# IRAUPS3.net
KiCad netlist of a schematic drawn in Altium Designer
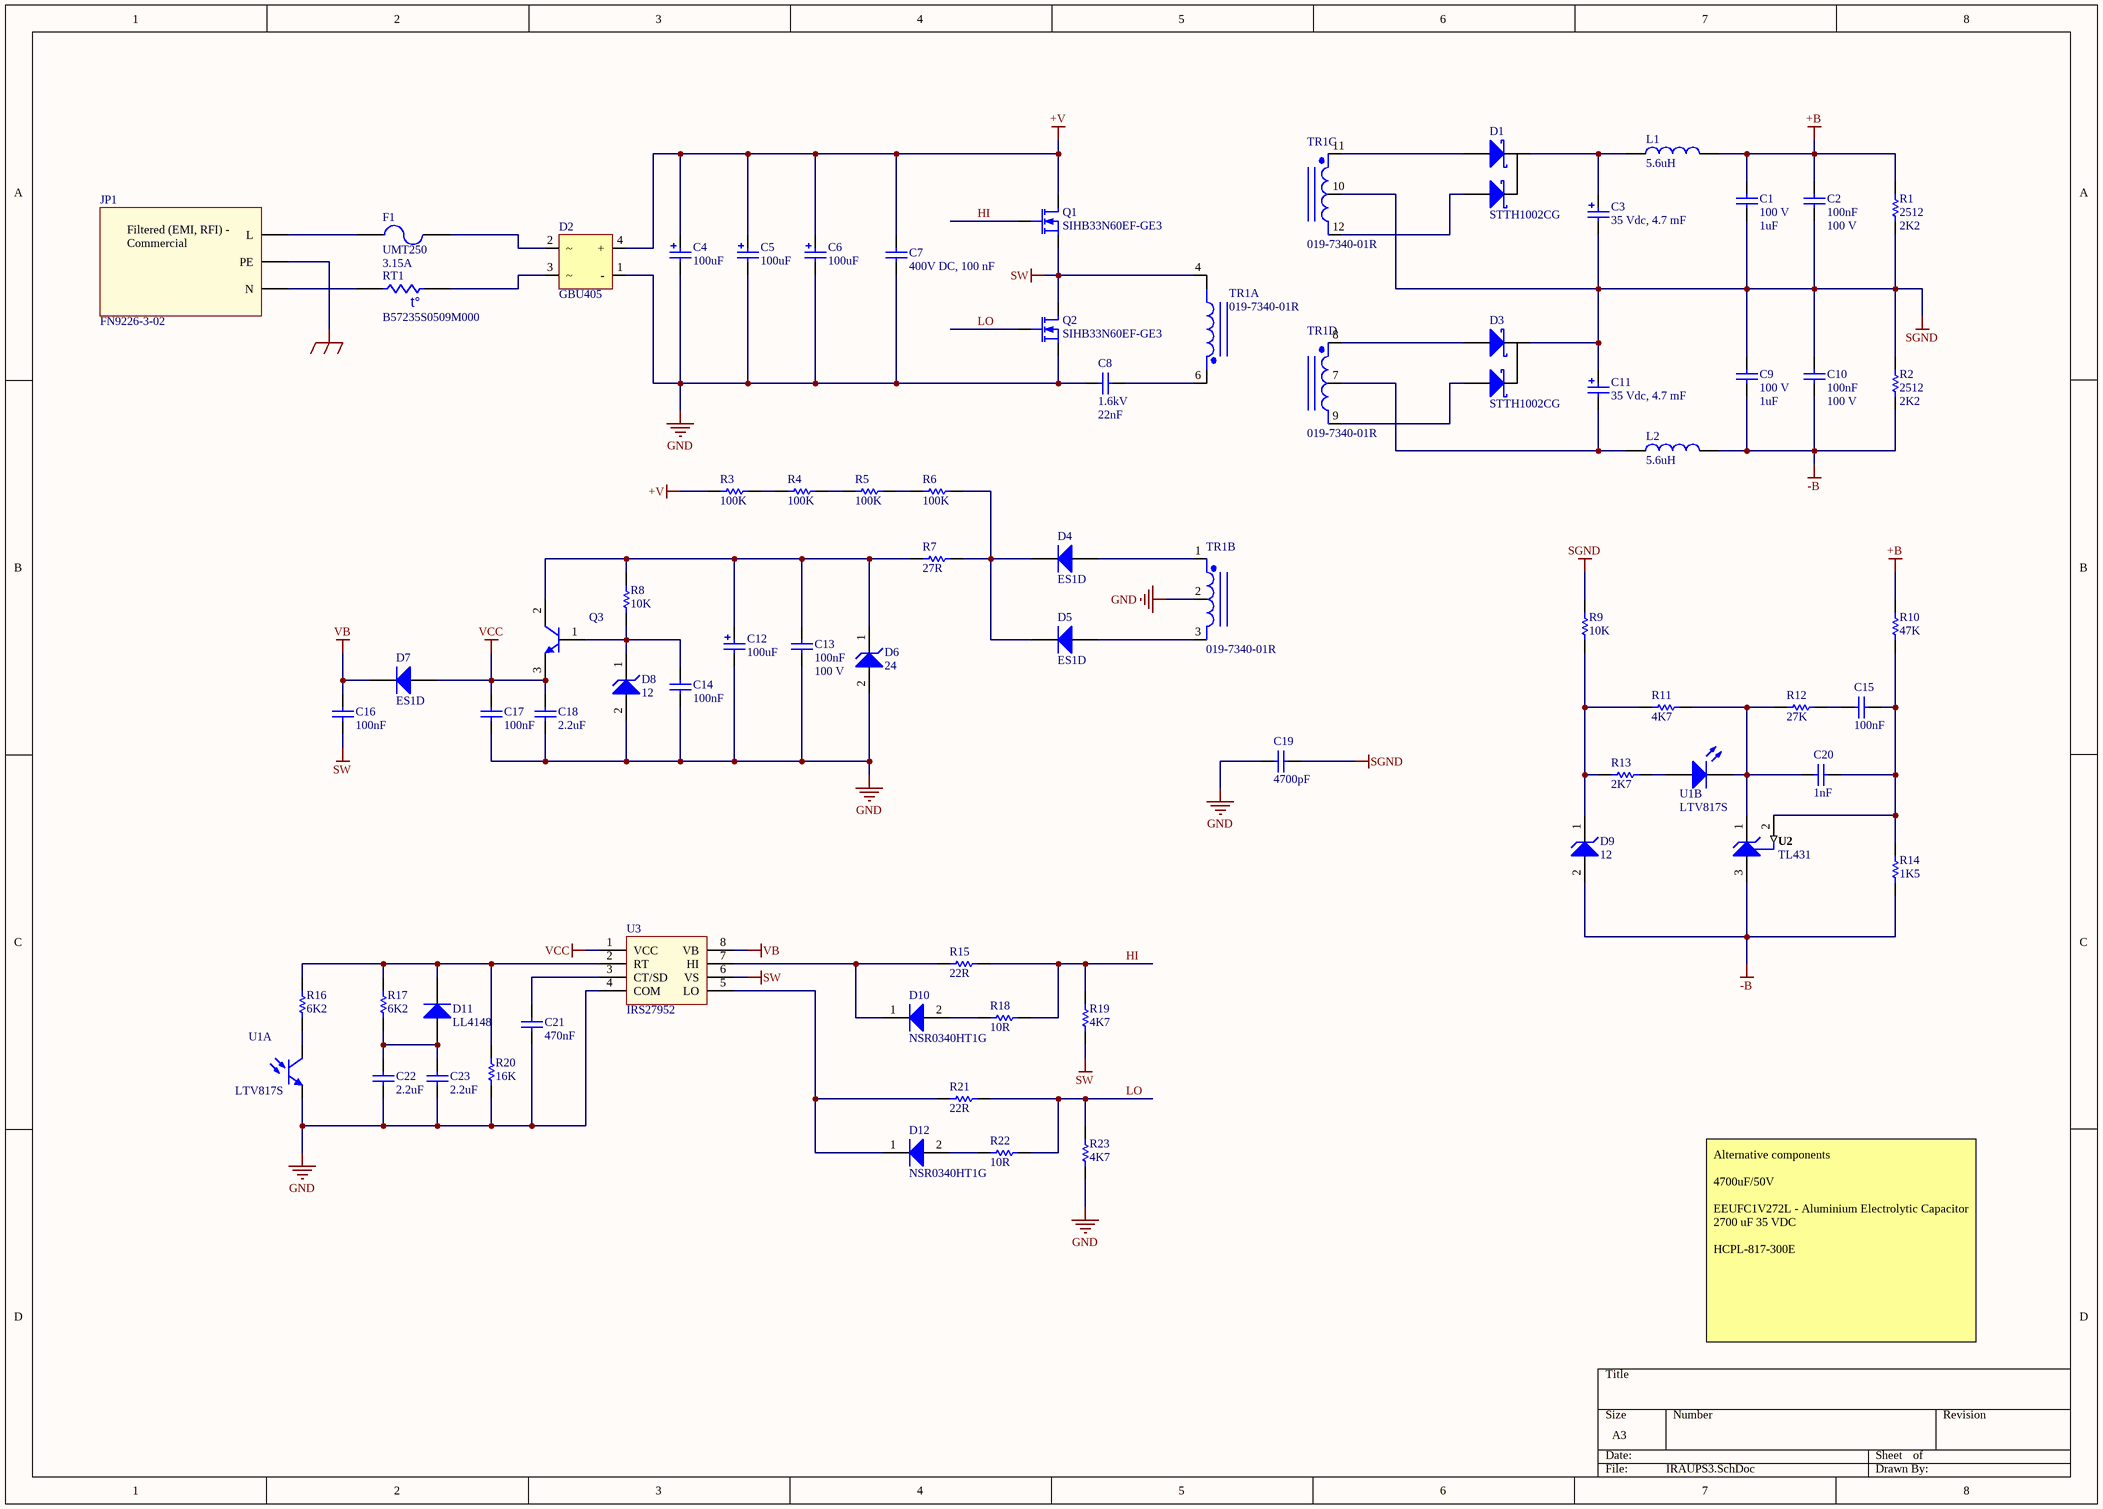
[diagram p0: IRAUPS3.SchDoc]

(export (version "E")
  (design (tool "Eeschema 10.0.6"))
  (components
    (comp (ref "C1")
      (value "1uF")
      (footprint "CAPC1206(3216)190_L")
      (description "CAP 1uF 100V ±20% 1206 (3216 Metric) Thickness 1.9mm SMD")
      (fields
        (field (name "RATED VOLTAGE") "100 V")
        (field (name "TOLERANCE") "Â±20%")
        (field (name "Comment") "CAP 1uF 100V 1206(3216)")
      )
      (libsource (lib "Altium Content Vault") (part "CAP"))
    )
    (comp (ref "C2")
      (value "100nF")
      (footprint "CAPC1206(3216)150_M")
      (description "CAP 100nF 100V ±20% 1206 (3216 Metric) Thickness 1.45mm SMD")
      (fields
        (field (name "TOLERANCE") "Â±20%")
        (field (name "RATED VOLTAGE") "100 V")
        (field (name "Comment") "CAP 100nF 100V 1206(3216)")
      )
      (libsource (lib "Altium Content Vault") (part "CAP"))
    )
    (comp (ref "C3")
      (value "35 Vdc, 4.7 mF")
      (footprint "WCAP-ATG8_18x35.5x7.5")
      (description "WCAP-ATG8 Aluminum Electrolytic Capacitors, 18x35.5mm, 35 Vdc, 4.7 mF")
      (fields (field (name "PART NUMBER") "860010581025") (field (name "PUBLISHER") "Wurth Elektronik"))
      (libsource (lib "ALTIUM-WCAP-ATG8-rev17a") (part "860010581025"))
    )
    (comp (ref "C4")
      (value "100uF")
      (footprint "WCAP-AT1H_16x35.5x7.5")
      (description "WCAP-AT1H Aluminum Electrolytic Capacitors, size Ф16x35.5mm, 450V DC, 100uF")
      (fields (field (name "PART NUMBER") "860241480001") (field (name "PUBLISHER") "Wurth Elektronik"))
      (libsource (lib "ALTIUM-WCAP-AT1H-rev17a") (part "860241480001"))
    )
    (comp (ref "C5")
      (value "100uF")
      (footprint "WCAP-AT1H_16x35.5x7.5")
      (description "WCAP-AT1H Aluminum Electrolytic Capacitors, size Ф16x35.5mm, 450V DC, 100uF")
      (fields (field (name "PART NUMBER") "860241480001") (field (name "PUBLISHER") "Wurth Elektronik"))
      (libsource (lib "ALTIUM-WCAP-AT1H-rev17a") (part "860241480001"))
    )
    (comp (ref "C6")
      (value "100uF")
      (footprint "WCAP-AT1H_16x35.5x7.5")
      (description "WCAP-AT1H Aluminum Electrolytic Capacitors, size Ф16x35.5mm, 450V DC, 100uF")
      (fields (field (name "PART NUMBER") "860241480001") (field (name "PUBLISHER") "Wurth Elektronik"))
      (libsource (lib "ALTIUM-WCAP-AT1H-rev17a") (part "860241480001"))
    )
    (comp (ref "C7")
      (value "400V DC, 100 nF")
      (footprint "WCAP-FTBE_13x5x11")
      (description "WCAP-FTBE Film Capacitors, 13x5x11mm, 400V DC, 100 nF")
      (fields (field (name "PART NUMBER") "890283423001CS") (field (name "PUBLISHER") "Wurth Elektronik"))
      (libsource (lib "ALTIUM-WCAP-FTBE-rev17a") (part "890283423001CS"))
    )
    (comp (ref "C8")
      (value "22nF")
      (footprint "CAP_RM15_W9L18")
      (description "0.022µF Film Capacitor 600V 1600V (1.6kV) Polypropylene (PP), Metallized Radial")
      (fields (field (name "MPN") "B32672L1223J000") (field (name "VOLTAGE") "1.6kV"))
      (libsource (lib "micun") (part "CAP_MKP_B32672L1223J000"))
    )
    (comp (ref "C9")
      (value "1uF")
      (footprint "CAPC1206(3216)190_L")
      (description "CAP 1uF 100V ±20% 1206 (3216 Metric) Thickness 1.9mm SMD")
      (fields
        (field (name "RATED VOLTAGE") "100 V")
        (field (name "TOLERANCE") "Â±20%")
        (field (name "Comment") "CAP 1uF 100V 1206(3216)")
      )
      (libsource (lib "Altium Content Vault") (part "CAP"))
    )
    (comp (ref "C10")
      (value "100nF")
      (footprint "CAPC1206(3216)150_M")
      (description "CAP 100nF 100V ±20% 1206 (3216 Metric) Thickness 1.45mm SMD")
      (fields
        (field (name "TOLERANCE") "Â±20%")
        (field (name "RATED VOLTAGE") "100 V")
        (field (name "Comment") "CAP 100nF 100V 1206(3216)")
      )
      (libsource (lib "Altium Content Vault") (part "CAP"))
    )
    (comp (ref "C11")
      (value "35 Vdc, 4.7 mF")
      (footprint "WCAP-ATG8_18x35.5x7.5")
      (description "WCAP-ATG8 Aluminum Electrolytic Capacitors, 18x35.5mm, 35 Vdc, 4.7 mF")
      (fields (field (name "PART NUMBER") "860010581025") (field (name "PUBLISHER") "Wurth Elektronik"))
      (libsource (lib "ALTIUM-WCAP-ATG8-rev17a") (part "860010581025"))
    )
    (comp (ref "C12")
      (value "100uF")
      (footprint "WCAP-AT1H_8x11.5x3.5")
      (description "WCAP-AT1H Aluminum Electrolytic Capacitors, size Ф8x11.5mm, 25V DC, 100uF")
      (fields (field (name "PART NUMBER") "860240474005") (field (name "PUBLISHER") "Wurth Elektronik"))
      (libsource (lib "ALTIUM-WCAP-AT1H-rev17a") (part "860240474005"))
    )
    (comp (ref "C13")
      (value "100nF")
      (footprint "CAPC1206(3216)150_M")
      (description "CAP 100nF 100V ±20% 1206 (3216 Metric) Thickness 1.45mm SMD")
      (fields
        (field (name "TOLERANCE") "Â±20%")
        (field (name "RATED VOLTAGE") "100 V")
        (field (name "Comment") "CAP 100nF 100V 1206(3216)")
      )
      (libsource (lib "Altium Content Vault") (part "CAP"))
    )
    (comp (ref "C14")
      (value "100nF")
      (footprint "CAPC0805(2012)100_N")
      (description "CAP 100nF 25V ±5% 0805 (2012 Metric) Thickness 1mm SMD")
      (fields (field (name "TOLERANCE") "Â±5%") (field (name "Comment") "CAP 100nF 25V 0805(2012)"))
      (libsource (lib "Altium Content Vault") (part "CAP"))
    )
    (comp (ref "C15")
      (value "100nF")
      (footprint "CAPC0805(2012)100_N")
      (description "CAP 100nF 25V ±5% 0805 (2012 Metric) Thickness 1mm SMD")
      (fields (field (name "TOLERANCE") "Â±5%") (field (name "Comment") "CAP 100nF 25V 0805(2012)"))
      (libsource (lib "Altium Content Vault") (part "CAP"))
    )
    (comp (ref "C16")
      (value "100nF")
      (footprint "CAPC0805(2012)100_N")
      (description "CAP 100nF 25V ±5% 0805 (2012 Metric) Thickness 1mm SMD")
      (fields (field (name "TOLERANCE") "Â±5%") (field (name "Comment") "CAP 100nF 25V 0805(2012)"))
      (libsource (lib "Altium Content Vault") (part "CAP"))
    )
    (comp (ref "C17")
      (value "100nF")
      (footprint "CAPC0805(2012)100_N")
      (description "CAP 100nF 25V ±5% 0805 (2012 Metric) Thickness 1mm SMD")
      (fields (field (name "TOLERANCE") "Â±5%") (field (name "Comment") "CAP 100nF 25V 0805(2012)"))
      (libsource (lib "Altium Content Vault") (part "CAP"))
    )
    (comp (ref "C18")
      (value "2.2uF")
      (footprint "CAPC0805(2012)145_N")
      (description "CAP 2.2uF 25V ±10% 0805 (2012 Metric) Thickness 1.45mm SMD")
      (fields (field (name "TOLERANCE") "Â±10%") (field (name "Comment") "CAP 2.2uF 25V 0805(2012)"))
      (libsource (lib "Altium Content Vault") (part "CAP"))
    )
    (comp (ref "C19")
      (value "4700pF")
      (footprint "CAP_VY2472M49Y5US63V7")
      (description "4700pF ±20% 440VAC Ceramic Capacitor Y5U (E) Radial, Disc")
      (fields (field (name "MPN") "VY2472M49Y5US63V7") (field (name "VOLTAGE") "440VAC"))
      (libsource (lib "micun") (part "CAP_VY2_4700"))
    )
    (comp (ref "C20")
      (value "1nF")
      (footprint "CAPC0805(2012)100_N")
      (description "CAP 1nF 25V ±10% 0805 (2012 Metric) Thickness 1mm SMD")
      (fields (field (name "TOLERANCE") "Â±10%") (field (name "Comment") "CAP 1nF 25V 0805(2012)"))
      (libsource (lib "Altium Content Vault") (part "CAP"))
    )
    (comp (ref "C21")
      (value "470nF")
      (footprint "CAPC0805(2012)100_N")
      (description "CAP 470nF 25V ±10% 0805 (2012 Metric) Thickness 1mm SMD")
      (fields (field (name "TOLERANCE") "Â±10%") (field (name "Comment") "CAP 470nF 25V 0805(2012)"))
      (libsource (lib "Altium Content Vault") (part "CAP"))
    )
    (comp (ref "C22")
      (value "2.2uF")
      (footprint "CAPC0805(2012)145_N")
      (description "CAP 2.2uF 25V ±10% 0805 (2012 Metric) Thickness 1.45mm SMD")
      (fields (field (name "TOLERANCE") "Â±10%") (field (name "Comment") "CAP 2.2uF 25V 0805(2012)"))
      (libsource (lib "Altium Content Vault") (part "CAP"))
    )
    (comp (ref "C23")
      (value "2.2uF")
      (footprint "CAPC0805(2012)145_N")
      (description "CAP 2.2uF 25V ±10% 0805 (2012 Metric) Thickness 1.45mm SMD")
      (fields (field (name "TOLERANCE") "Â±10%") (field (name "Comment") "CAP 2.2uF 25V 0805(2012)"))
      (libsource (lib "Altium Content Vault") (part "CAP"))
    )
    (comp (ref "D1")
      (value "STTH1002CG")
      (footprint "TO-263_L")
      (description "Diode Array 1 Pair Common Cathode Schottky 60V 15A Through Hole TO-220-3")
      (libsource (lib "micun") (part "DIODE-STTH1002CG"))
    )
    (comp (ref "D2")
      (value "GBU405")
      (footprint "DIOD_BRIDGE_GBU")
      (description "IC RECT BRIDGE 0.5A 600V 4SOIC")
      (libsource (lib "micun") (part "DIOD_BRIDGE_GBU405"))
    )
    (comp (ref "D3")
      (value "STTH1002CG")
      (footprint "TO-263_L")
      (description "Diode Array 1 Pair Common Cathode Schottky 60V 15A Through Hole TO-220-3")
      (libsource (lib "micun") (part "DIODE-STTH1002CG"))
    )
    (comp (ref "D4")
      (value "ES1D")
      (footprint "FAIR-SMA-2_V")
      (description "Fairchild ES1D Diode, 200 V, 1 A, -50 to 150 degC, 2-Pin SMA, RoHS, Cut Tape")
      (fields (field (name "MANUFACTURER") "Fairchild Semiconductor"))
      (libsource (lib "Altium Content Vault") (part "D-KA-2"))
    )
    (comp (ref "D5")
      (value "ES1D")
      (footprint "FAIR-SMA-2_V")
      (description "Fairchild ES1D Diode, 200 V, 1 A, -50 to 150 degC, 2-Pin SMA, RoHS, Cut Tape")
      (fields (field (name "MANUFACTURER") "Fairchild Semiconductor"))
      (libsource (lib "Altium Content Vault") (part "D-KA-2"))
    )
    (comp (ref "D6")
      (value "1SMA5934BT3G")
      (footprint "ONSC-SMA-2-403D-02_F_V")
      (description "1.5 W Zener Voltage Regulator, 2-Pin SMA, Pb-Free, Tape and Reel")
      (fields (field (name "VZ TYP (V)") "24") (field (name "MANUFACTURER") "On Semiconductor"))
      (libsource (lib "Altium Content Vault") (part "ONSC-K1A2-2"))
    )
    (comp (ref "D7")
      (value "ES1D")
      (footprint "FAIR-SMA-2_V")
      (description "Fairchild ES1D Diode, 200 V, 1 A, -50 to 150 degC, 2-Pin SMA, RoHS, Cut Tape")
      (fields (field (name "MANUFACTURER") "Fairchild Semiconductor"))
      (libsource (lib "Altium Content Vault") (part "D-KA-2"))
    )
    (comp (ref "D8")
      (value "1SMA5927BT3G")
      (footprint "ONSC-SMA-2-403D-02_F_V")
      (description "1.5 W Zener Voltage Regulator, 2-Pin SMA, Pb-Free, Tape and Reel")
      (fields (field (name "VZ TYP (V)") "12") (field (name "MANUFACTURER") "On Semiconductor"))
      (libsource (lib "Altium Content Vault") (part "ONSC-K1A2-2"))
    )
    (comp (ref "D9")
      (value "1SMA5927BT3G")
      (footprint "ONSC-SMA-2-403D-02_F_V")
      (description "1.5 W Zener Voltage Regulator, 2-Pin SMA, Pb-Free, Tape and Reel")
      (fields (field (name "VZ TYP (V)") "12") (field (name "MANUFACTURER") "On Semiconductor"))
      (libsource (lib "Altium Content Vault") (part "ONSC-K1A2-2"))
    )
    (comp (ref "D10")
      (value "NSR0340HT1G")
      (footprint "ONSC-SOD-323-2-477-02_V")
      (description "Schottky Barrier Diode, 2-Pin SOD-323, Pb-Free, Tape and Reel")
      (fields (field (name "MANUFACTURER") "On Semiconductor"))
      (libsource (lib "Altium Content Vault") (part "ONSC-D-K1A2-2"))
    )
    (comp (ref "D11")
      (value "LL4148")
      (footprint "DIOD-SOD-80")
      (description "DIODE GEN PURP 100V 200MA SOD80")
      (libsource (lib "micun") (part "DIOD_GP_LL4148"))
    )
    (comp (ref "D12")
      (value "NSR0340HT1G")
      (footprint "ONSC-SOD-323-2-477-02_V")
      (description "Schottky Barrier Diode, 2-Pin SOD-323, Pb-Free, Tape and Reel")
      (fields (field (name "MANUFACTURER") "On Semiconductor"))
      (libsource (lib "Altium Content Vault") (part "ONSC-D-K1A2-2"))
    )
    (comp (ref "F1")
      (value "UMT250")
      (footprint "FUSE_UMT250")
      (description "Fuse")
      (fields (field (name "MPN") "3403.0171.11") (field (name "ALTIUM_VALUE") "3.15A"))
      (libsource (lib "micun") (part "FUSE_UMT250-3.15A"))
    )
    (comp (ref "JP1")
      (value "FN9226-3-02")
      (footprint "CONN-FN9226-3-02")
      (libsource (lib "micun") (part "CONN_FN9226-3-02"))
    )
    (comp (ref "L1")
      (value "5.6uH")
      (footprint "WE-HCI_5040_WE-PERM 2")
      (description "WE-HCI SMD Flat Wire High Current Inductor, size 5040, 4.5A, 5.6uH")
      (fields (field (name "PART NUMBER") "744316560") (field (name "PUBLISHER") "Wurth Elektronik"))
      (libsource (lib "ALTIUM-WE-HCI-rev17a") (part "744316560"))
    )
    (comp (ref "L2")
      (value "5.6uH")
      (footprint "WE-HCI_5040_WE-PERM 2")
      (description "WE-HCI SMD Flat Wire High Current Inductor, size 5040, 4.5A, 5.6uH")
      (fields (field (name "PART NUMBER") "744316560") (field (name "PUBLISHER") "Wurth Elektronik"))
      (libsource (lib "ALTIUM-WE-HCI-rev17a") (part "744316560"))
    )
    (comp (ref "Q1")
      (value "SIHB33N60EF-GE3")
      (footprint "D2PAK_L")
      (description "N-Channel 600V 33A (Tc) 278W (Tc) Surface Mount D²PAK (TO-263)")
      (libsource (lib "micun") (part "TRAN_SIHB33N60EF-GE3"))
    )
    (comp (ref "Q2")
      (value "SIHB33N60EF-GE3")
      (footprint "D2PAK_L")
      (description "N-Channel 600V 33A (Tc) 278W (Tc) Surface Mount D²PAK (TO-263)")
      (libsource (lib "micun") (part "TRAN_SIHB33N60EF-GE3"))
    )
    (comp (ref "Q3")
      (value "2SC5569-TD-E")
      (footprint "ONSC-SOT-89-3-419AW_V")
      (description "Bipolar Transistor, 50 V, 7 A, Low VCE(sat), NPN Single, 3-Pin SOT-89, Pb-Free, Tape and Reel")
      (fields (field (name "MANUFACTURER") "On Semiconductor"))
      (libsource (lib "Altium Content Vault") (part "ONSC-NPN-B1C2E3-3_C"))
    )
    (comp (ref "R1")
      (value "2K2")
      (footprint "RESC2512(6432)_L")
      (description "2K2 1W 5% 2512 (6432 Metric)  SMD")
      (fields (field (name "POWER") "1 W") (field (name "CASE-EIA") "2512") (field (name "TOLERANCE") "5 %"))
      (libsource (lib "Altium Content Vault") (part "RES"))
    )
    (comp (ref "R2")
      (value "2K2")
      (footprint "RESC2512(6432)_L")
      (description "2K2 1W 5% 2512 (6432 Metric)  SMD")
      (fields (field (name "POWER") "1 W") (field (name "CASE-EIA") "2512") (field (name "TOLERANCE") "5 %"))
      (libsource (lib "Altium Content Vault") (part "RES"))
    )
    (comp (ref "R3")
      (value "100K")
      (footprint "RESC1206(3216)_N")
      (description "100K 0.25W 5% 1206 (3216 Metric)  SMD")
      (fields (field (name "POWER") "0.25 W") (field (name "TOLERANCE") "5 %"))
      (libsource (lib "Altium Content Vault") (part "RES"))
    )
    (comp (ref "R4")
      (value "100K")
      (footprint "RESC1206(3216)_N")
      (description "100K 0.25W 5% 1206 (3216 Metric)  SMD")
      (fields (field (name "POWER") "0.25 W") (field (name "TOLERANCE") "5 %"))
      (libsource (lib "Altium Content Vault") (part "RES"))
    )
    (comp (ref "R5")
      (value "100K")
      (footprint "RESC1206(3216)_N")
      (description "100K 0.25W 5% 1206 (3216 Metric)  SMD")
      (fields (field (name "POWER") "0.25 W") (field (name "TOLERANCE") "5 %"))
      (libsource (lib "Altium Content Vault") (part "RES"))
    )
    (comp (ref "R6")
      (value "100K")
      (footprint "RESC1206(3216)_N")
      (description "100K 0.25W 5% 1206 (3216 Metric)  SMD")
      (fields (field (name "POWER") "0.25 W") (field (name "TOLERANCE") "5 %"))
      (libsource (lib "Altium Content Vault") (part "RES"))
    )
    (comp (ref "R7")
      (value "27R")
      (footprint "RESC0805(2012)_N")
      (description "27R 0.125W 5% 0805 (2012 Metric)  SMD")
      (fields (field (name "TOLERANCE") "5 %") (field (name "POWER") "0.125 W"))
      (libsource (lib "Altium Content Vault") (part "RES"))
    )
    (comp (ref "R8")
      (value "10K")
      (footprint "RESC0805(2012)_N")
      (description "10K 0.125W 5% 0805 (2012 Metric)  SMD")
      (fields (field (name "POWER") "0.125 W") (field (name "TOLERANCE") "5 %"))
      (libsource (lib "Altium Content Vault") (part "RES"))
    )
    (comp (ref "R9")
      (value "10K")
      (footprint "RESC0805(2012)_N")
      (description "10K 0.125W 5% 0805 (2012 Metric)  SMD")
      (fields (field (name "POWER") "0.125 W") (field (name "TOLERANCE") "5 %"))
      (libsource (lib "Altium Content Vault") (part "RES"))
    )
    (comp (ref "R10")
      (value "47K")
      (footprint "RESC0805(2012)_N")
      (description "47K 0.125W 5% 0805 (2012 Metric)  SMD")
      (fields (field (name "TOLERANCE") "5 %") (field (name "POWER") "0.125 W"))
      (libsource (lib "Altium Content Vault") (part "RES"))
    )
    (comp (ref "R11")
      (value "4K7")
      (footprint "RESC0805(2012)_N")
      (description "4K7 0.125W 5% 0805 (2012 Metric)  SMD")
      (fields (field (name "POWER") "0.125 W") (field (name "TOLERANCE") "5 %"))
      (libsource (lib "Altium Content Vault") (part "RES"))
    )
    (comp (ref "R12")
      (value "27K")
      (footprint "RESC0805(2012)_N")
      (description "27K 0.125W 5% 0805 (2012 Metric)  SMD")
      (fields (field (name "POWER") "0.125 W") (field (name "TOLERANCE") "5 %"))
      (libsource (lib "Altium Content Vault") (part "RES"))
    )
    (comp (ref "R13")
      (value "2K7")
      (footprint "RESC0805(2012)_N")
      (description "2K7 0.125W 5% 0805 (2012 Metric)  SMD")
      (fields (field (name "POWER") "0.125 W") (field (name "TOLERANCE") "5 %"))
      (libsource (lib "Altium Content Vault") (part "RES"))
    )
    (comp (ref "R14")
      (value "1K5")
      (footprint "RESC0805(2012)_L")
      (description "1K5 0.125W 5% 0805 (2012 Metric)  SMD")
      (fields (field (name "POWER") "0.125 W") (field (name "TOLERANCE") "5 %"))
      (libsource (lib "Altium Content Vault") (part "RES"))
    )
    (comp (ref "R15")
      (value "22R")
      (footprint "RESC0805(2012)_N")
      (description "22R 0.125W 5% 0805 (2012 Metric)  SMD")
      (fields (field (name "POWER") "0.125 W") (field (name "TOLERANCE") "5 %"))
      (libsource (lib "Altium Content Vault") (part "RES"))
    )
    (comp (ref "R16")
      (value "6K2")
      (footprint "RESC0805(2012)_N")
      (description "6K2 0.125W 1% 0805 (2012 Metric)  SMD")
      (fields (field (name "POWER") "0.125 W") (field (name "TOLERANCE") "1 %"))
      (libsource (lib "Altium Content Vault") (part "RES"))
    )
    (comp (ref "R17")
      (value "6K2")
      (footprint "RESC0805(2012)_N")
      (description "6K2 0.125W 1% 0805 (2012 Metric)  SMD")
      (fields (field (name "POWER") "0.125 W") (field (name "TOLERANCE") "1 %"))
      (libsource (lib "Altium Content Vault") (part "RES"))
    )
    (comp (ref "R18")
      (value "10R")
      (footprint "RESC0805(2012)_N")
      (description "10R 0.125W 5% 0805 (2012 Metric)  SMD")
      (fields (field (name "POWER") "0.125 W") (field (name "TOLERANCE") "5 %"))
      (libsource (lib "Altium Content Vault") (part "RES"))
    )
    (comp (ref "R19")
      (value "4K7")
      (footprint "RESC0805(2012)_N")
      (description "4K7 0.125W 5% 0805 (2012 Metric)  SMD")
      (fields (field (name "POWER") "0.125 W") (field (name "TOLERANCE") "5 %"))
      (libsource (lib "Altium Content Vault") (part "RES"))
    )
    (comp (ref "R20")
      (value "16K")
      (footprint "RESC0805(2012)_N")
      (description "16K 0.125W 1% 0805 (2012 Metric)  SMD")
      (fields (field (name "TOLERANCE") "1 %") (field (name "POWER") "0.125 W"))
      (libsource (lib "Altium Content Vault") (part "RES"))
    )
    (comp (ref "R21")
      (value "22R")
      (footprint "RESC0805(2012)_N")
      (description "22R 0.125W 5% 0805 (2012 Metric)  SMD")
      (fields (field (name "POWER") "0.125 W") (field (name "TOLERANCE") "5 %"))
      (libsource (lib "Altium Content Vault") (part "RES"))
    )
    (comp (ref "R22")
      (value "10R")
      (footprint "RESC0805(2012)_N")
      (description "10R 0.125W 5% 0805 (2012 Metric)  SMD")
      (fields (field (name "POWER") "0.125 W") (field (name "TOLERANCE") "5 %"))
      (libsource (lib "Altium Content Vault") (part "RES"))
    )
    (comp (ref "R23")
      (value "4K7")
      (footprint "RESC0805(2012)_N")
      (description "4K7 0.125W 5% 0805 (2012 Metric)  SMD")
      (fields (field (name "POWER") "0.125 W") (field (name "TOLERANCE") "5 %"))
      (libsource (lib "Altium Content Vault") (part "RES"))
    )
    (comp (ref "RT1")
      (value "B57235S0509M000")
      (footprint "RES_TH_9.5mm")
      (description "Inrush Current Limiter 5 Ohms ±20% 4.2A 0.374\" (9.50mm)")
      (libsource (lib "micun") (part "RES_B57235S0509M000"))
    )
    (comp (ref "TR1")
      (value "019-7340-01R")
      (footprint "TRAN_019-7340-01R")
      (description "LLC transformer")
      (libsource (lib "micun") (part "TRANS_019-7340-01R"))
    )
    (comp (ref "U1")
      (value "LTV817S")
      (footprint "SMD-4")
      (description "Optoisolator Transistor Output 5000Vrms 1 Channel 4-SMD")
      (libsource (lib "micun") (part "OPTO-LTV817S"))
    )
    (comp (ref "U2")
      (value "TL431")
      (footprint "DBZ0003A_M")
      (fields (field (name "PARTNUMBER") "TL431AQDBZRQ1") (field (name "MANUFACTURER") "Texas Instruments"))
      (libsource (lib "Altium Content Vault") (part "TI-TL431A-Q1DBZ3"))
    )
    (comp (ref "U3")
      (value "IRS27952")
      (footprint "SOIC8_L")
      (description "IC REG CTRLR BUCK/HALF-BRG 8SOIC")
      (fields (field (name "MPN") "IRS27952SPBF"))
      (libsource (lib "micun") (part "IC-PMIC-IRS27952"))
    )
  )
  (nets
    (net (code "1") (name "+B") (class "Default")
      (node (ref "C1") (pin "2") (pinfunction "2_2") (pintype "passive"))
      (node (ref "C2") (pin "2") (pinfunction "2_2") (pintype "passive"))
      (node (ref "L1") (pin "2") (pinfunction "2_2") (pintype "passive"))
      (node (ref "R1") (pin "2") (pinfunction "2_2") (pintype "passive"))
      (node (ref "R10") (pin "2") (pinfunction "2_2") (pintype "passive"))
    )
    (net (code "2") (name "+V") (class "Default")
      (node (ref "C4") (pin "1") (pinfunction "P_1") (pintype "passive"))
      (node (ref "C5") (pin "1") (pinfunction "P_1") (pintype "passive"))
      (node (ref "C6") (pin "1") (pinfunction "P_1") (pintype "passive"))
      (node (ref "C7") (pin "2") (pinfunction "2_2") (pintype "passive"))
      (node (ref "D2") (pin "4") (pinfunction "+_4") (pintype "passive"))
      (node (ref "Q1") (pin "4") (pinfunction "D_4") (pintype "passive"))
      (node (ref "R3") (pin "2") (pinfunction "2_2") (pintype "passive"))
    )
    (net (code "3") (name "-B") (class "Default")
      (node (ref "C10") (pin "1") (pinfunction "1_1") (pintype "passive"))
      (node (ref "C9") (pin "1") (pinfunction "1_1") (pintype "passive"))
      (node (ref "D9") (pin "2") (pinfunction "A_2") (pintype "passive"))
      (node (ref "L2") (pin "2") (pinfunction "2_2") (pintype "passive"))
      (node (ref "R14") (pin "2") (pinfunction "2_2") (pintype "passive"))
      (node (ref "R2") (pin "1") (pinfunction "1_1") (pintype "passive"))
      (node (ref "U2") (pin "3") (pinfunction "ANODE_3") (pintype "power_in"))
    )
    (net (code "4") (name "/HI") (class "Default")
      (node (ref "Q1") (pin "1") (pinfunction "G_1") (pintype "passive"))
      (node (ref "R15") (pin "2") (pinfunction "2_2") (pintype "passive"))
      (node (ref "R18") (pin "2") (pinfunction "2_2") (pintype "passive"))
      (node (ref "R19") (pin "2") (pinfunction "2_2") (pintype "passive"))
    )
    (net (code "5") (name "/LO") (class "Default")
      (node (ref "Q2") (pin "1") (pinfunction "G_1") (pintype "passive"))
      (node (ref "R21") (pin "2") (pinfunction "2_2") (pintype "passive"))
      (node (ref "R22") (pin "2") (pinfunction "2_2") (pintype "passive"))
      (node (ref "R23") (pin "2") (pinfunction "2_2") (pintype "passive"))
    )
    (net (code "6") (name "GND") (class "Default")
      (node (ref "C12") (pin "2") (pinfunction "N_2") (pintype "passive"))
      (node (ref "C13") (pin "1") (pinfunction "1_1") (pintype "passive"))
      (node (ref "C14") (pin "1") (pinfunction "1_1") (pintype "passive"))
      (node (ref "C17") (pin "1") (pinfunction "1_1") (pintype "passive"))
      (node (ref "C18") (pin "1") (pinfunction "1_1") (pintype "passive"))
      (node (ref "C19") (pin "1") (pinfunction "1_1") (pintype "passive"))
      (node (ref "C21") (pin "1") (pinfunction "1_1") (pintype "passive"))
      (node (ref "C22") (pin "1") (pinfunction "1_1") (pintype "passive"))
      (node (ref "C23") (pin "1") (pinfunction "1_1") (pintype "passive"))
      (node (ref "C4") (pin "2") (pinfunction "N_2") (pintype "passive"))
      (node (ref "C5") (pin "2") (pinfunction "N_2") (pintype "passive"))
      (node (ref "C6") (pin "2") (pinfunction "N_2") (pintype "passive"))
      (node (ref "C7") (pin "1") (pinfunction "1_1") (pintype "passive"))
      (node (ref "C8") (pin "1") (pinfunction "1_1") (pintype "passive"))
      (node (ref "D2") (pin "1") (pinfunction "-_1") (pintype "passive"))
      (node (ref "D6") (pin "2") (pinfunction "A_2") (pintype "passive"))
      (node (ref "D8") (pin "2") (pinfunction "A_2") (pintype "passive"))
      (node (ref "Q2") (pin "3") (pinfunction "S_3") (pintype "passive"))
      (node (ref "R20") (pin "1") (pinfunction "1_1") (pintype "passive"))
      (node (ref "R23") (pin "1") (pinfunction "1_1") (pintype "passive"))
      (node (ref "TR1") (pin "2") (pinfunction "2_2") (pintype "passive"))
      (node (ref "U1") (pin "3") (pinfunction "E_3") (pintype "passive"))
      (node (ref "U3") (pin "4") (pinfunction "COM_4") (pintype "power_in"))
    )
    (net (code "7") (name "Net-(C3-P)") (class "Default")
      (node (ref "C3") (pin "1") (pinfunction "P_1") (pintype "passive"))
      (node (ref "D1") (pin "4") (pinfunction "K_4") (pintype "passive"))
      (node (ref "L1") (pin "1") (pinfunction "1_1") (pintype "passive"))
    )
    (net (code "8") (name "Net-(C11-N)") (class "Default")
      (node (ref "C11") (pin "2") (pinfunction "N_2") (pintype "passive"))
      (node (ref "L2") (pin "1") (pinfunction "1_1") (pintype "passive"))
      (node (ref "TR1") (pin "7") (pinfunction "7_7") (pintype "passive"))
    )
    (net (code "9") (name "Net-(C12-P)") (class "Default")
      (node (ref "C12") (pin "1") (pinfunction "P_1") (pintype "passive"))
      (node (ref "C13") (pin "2") (pinfunction "2_2") (pintype "passive"))
      (node (ref "D6") (pin "1") (pinfunction "K_1") (pintype "passive"))
      (node (ref "Q3") (pin "2") (pinfunction "C_2") (pintype "passive"))
      (node (ref "R7") (pin "2") (pinfunction "2_2") (pintype "passive"))
      (node (ref "R8") (pin "2") (pinfunction "2_2") (pintype "passive"))
    )
    (net (code "10") (name "Net-(C15-Pad1)") (class "Default")
      (node (ref "C15") (pin "1") (pinfunction "1_1") (pintype "passive"))
      (node (ref "R12") (pin "2") (pinfunction "2_2") (pintype "passive"))
    )
    (net (code "11") (name "Net-(D1-A1)") (class "Default")
      (node (ref "D1") (pin "1") (pinfunction "A1_1") (pintype "passive"))
      (node (ref "TR1") (pin "11") (pinfunction "11_11") (pintype "passive"))
    )
    (net (code "12") (name "Net-(D1-A2)") (class "Default")
      (node (ref "D1") (pin "3") (pinfunction "A2_3") (pintype "passive"))
      (node (ref "TR1") (pin "12") (pinfunction "12_12") (pintype "passive"))
    )
    (net (code "13") (name "Net-(D2-~-Pad2)") (class "Default")
      (node (ref "D2") (pin "2") (pinfunction "~_2") (pintype "passive"))
      (node (ref "F1") (pin "2") (pinfunction "2_2") (pintype "passive"))
    )
    (net (code "14") (name "Net-(D2-~-Pad3)") (class "Default")
      (node (ref "D2") (pin "3") (pinfunction "~_3") (pintype "passive"))
      (node (ref "RT1") (pin "1") (pinfunction "1_1") (pintype "passive"))
    )
    (net (code "15") (name "Net-(D3-A1)") (class "Default")
      (node (ref "D3") (pin "1") (pinfunction "A1_1") (pintype "passive"))
      (node (ref "TR1") (pin "8") (pinfunction "8_8") (pintype "passive"))
    )
    (net (code "16") (name "Net-(D3-A2)") (class "Default")
      (node (ref "D3") (pin "3") (pinfunction "A2_3") (pintype "passive"))
      (node (ref "TR1") (pin "9") (pinfunction "9_9") (pintype "passive"))
    )
    (net (code "17") (name "Net-(D4-A)") (class "Default")
      (node (ref "D4") (pin "2") (pinfunction "A_2") (pintype "passive"))
      (node (ref "TR1") (pin "1") (pinfunction "1_1") (pintype "passive"))
    )
    (net (code "18") (name "Net-(D4-K)") (class "Default")
      (node (ref "D4") (pin "1") (pinfunction "K_1") (pintype "passive"))
      (node (ref "D5") (pin "1") (pinfunction "K_1") (pintype "passive"))
      (node (ref "R6") (pin "1") (pinfunction "1_1") (pintype "passive"))
      (node (ref "R7") (pin "1") (pinfunction "1_1") (pintype "passive"))
    )
    (net (code "19") (name "Net-(D5-A)") (class "Default")
      (node (ref "D5") (pin "2") (pinfunction "A_2") (pintype "passive"))
      (node (ref "TR1") (pin "3") (pinfunction "3_3") (pintype "passive"))
    )
    (net (code "20") (name "Net-(D8-K)") (class "Default")
      (node (ref "C14") (pin "2") (pinfunction "2_2") (pintype "passive"))
      (node (ref "D8") (pin "1") (pinfunction "K_1") (pintype "passive"))
      (node (ref "Q3") (pin "1") (pinfunction "B_1") (pintype "passive"))
      (node (ref "R8") (pin "1") (pinfunction "1_1") (pintype "passive"))
    )
    (net (code "21") (name "Net-(D9-K)") (class "Default")
      (node (ref "D9") (pin "1") (pinfunction "K_1") (pintype "passive"))
      (node (ref "R11") (pin "2") (pinfunction "2_2") (pintype "passive"))
      (node (ref "R13") (pin "2") (pinfunction "2_2") (pintype "passive"))
      (node (ref "R9") (pin "1") (pinfunction "1_1") (pintype "passive"))
    )
    (net (code "22") (name "Net-(D10-A)") (class "Default")
      (node (ref "D10") (pin "2") (pinfunction "A_2") (pintype "passive"))
      (node (ref "R18") (pin "1") (pinfunction "1_1") (pintype "passive"))
    )
    (net (code "23") (name "Net-(D10-K)") (class "Default")
      (node (ref "D10") (pin "1") (pinfunction "K_1") (pintype "passive"))
      (node (ref "R15") (pin "1") (pinfunction "1_1") (pintype "passive"))
      (node (ref "U3") (pin "7") (pinfunction "HI_7") (pintype "passive"))
    )
    (net (code "24") (name "Net-(D11-A)") (class "Default")
      (node (ref "C22") (pin "2") (pinfunction "2_2") (pintype "passive"))
      (node (ref "C23") (pin "2") (pinfunction "2_2") (pintype "passive"))
      (node (ref "D11") (pin "1") (pinfunction "A_1") (pintype "passive"))
      (node (ref "R17") (pin "1") (pinfunction "1_1") (pintype "passive"))
    )
    (net (code "25") (name "Net-(D11-K)") (class "Default")
      (node (ref "D11") (pin "2") (pinfunction "K_2") (pintype "passive"))
      (node (ref "R16") (pin "2") (pinfunction "2_2") (pintype "passive"))
      (node (ref "R17") (pin "2") (pinfunction "2_2") (pintype "passive"))
      (node (ref "R20") (pin "2") (pinfunction "2_2") (pintype "passive"))
      (node (ref "U3") (pin "2") (pinfunction "RT_2") (pintype "passive"))
    )
    (net (code "26") (name "Net-(D12-A)") (class "Default")
      (node (ref "D12") (pin "2") (pinfunction "A_2") (pintype "passive"))
      (node (ref "R22") (pin "1") (pinfunction "1_1") (pintype "passive"))
    )
    (net (code "27") (name "Net-(D12-K)") (class "Default")
      (node (ref "D12") (pin "1") (pinfunction "K_1") (pintype "passive"))
      (node (ref "R21") (pin "1") (pinfunction "1_1") (pintype "passive"))
      (node (ref "U3") (pin "5") (pinfunction "LO_5") (pintype "passive"))
    )
    (net (code "28") (name "Net-(F1-Pad1)") (class "Default")
      (node (ref "F1") (pin "1") (pinfunction "1_1") (pintype "passive"))
      (node (ref "JP1") (pin "L") (pinfunction "L_L") (pintype "power_in"))
    )
    (net (code "29") (name "Net-(JP1-PadN)") (class "Default")
      (node (ref "JP1") (pin "N") (pinfunction "N_N") (pintype "power_in"))
      (node (ref "RT1") (pin "2") (pinfunction "2_2") (pintype "passive"))
    )
    (net (code "30") (name "Net-(R3-Pad1)") (class "Default")
      (node (ref "R3") (pin "1") (pinfunction "1_1") (pintype "passive"))
      (node (ref "R4") (pin "2") (pinfunction "2_2") (pintype "passive"))
    )
    (net (code "31") (name "Net-(R4-Pad1)") (class "Default")
      (node (ref "R4") (pin "1") (pinfunction "1_1") (pintype "passive"))
      (node (ref "R5") (pin "2") (pinfunction "2_2") (pintype "passive"))
    )
    (net (code "32") (name "Net-(R5-Pad1)") (class "Default")
      (node (ref "R5") (pin "1") (pinfunction "1_1") (pintype "passive"))
      (node (ref "R6") (pin "2") (pinfunction "2_2") (pintype "passive"))
    )
    (net (code "33") (name "Net-(TR1A-2)") (class "Default")
      (node (ref "C8") (pin "2") (pinfunction "2_2") (pintype "passive"))
      (node (ref "TR1") (pin "6") (pinfunction "2_6") (pintype "passive"))
    )
    (net (code "34") (name "Net-(U1A-C)") (class "Default")
      (node (ref "R16") (pin "1") (pinfunction "1_1") (pintype "passive"))
      (node (ref "U1") (pin "4") (pinfunction "C_4") (pintype "passive"))
    )
    (net (code "35") (name "Net-(U1B-A)") (class "Default")
      (node (ref "R13") (pin "1") (pinfunction "1_1") (pintype "passive"))
      (node (ref "U1") (pin "1") (pinfunction "A_1") (pintype "passive"))
    )
    (net (code "36") (name "Net-(U1B-K)") (class "Default")
      (node (ref "C20") (pin "1") (pinfunction "1_1") (pintype "passive"))
      (node (ref "R11") (pin "1") (pinfunction "1_1") (pintype "passive"))
      (node (ref "R12") (pin "1") (pinfunction "1_1") (pintype "passive"))
      (node (ref "U1") (pin "2") (pinfunction "K_2") (pintype "passive"))
      (node (ref "U2") (pin "1") (pinfunction "CATHODE_1") (pintype "passive"))
    )
    (net (code "37") (name "Net-(U2-REF)") (class "Default")
      (node (ref "C15") (pin "2") (pinfunction "2_2") (pintype "passive"))
      (node (ref "C20") (pin "2") (pinfunction "2_2") (pintype "passive"))
      (node (ref "R10") (pin "1") (pinfunction "1_1") (pintype "passive"))
      (node (ref "R14") (pin "1") (pinfunction "1_1") (pintype "passive"))
      (node (ref "U2") (pin "2") (pinfunction "REF_2") (pintype "input"))
    )
    (net (code "38") (name "Net-(U3-CT{slash}SD)") (class "Default")
      (node (ref "C21") (pin "2") (pinfunction "2_2") (pintype "passive"))
      (node (ref "U3") (pin "3") (pinfunction "CT/SD_3") (pintype "passive"))
    )
    (net (code "39") (name "PE") (class "Default")
      (node (ref "JP1") (pin "PE") (pinfunction "PE_PE") (pintype "power_in"))
    )
    (net (code "40") (name "SGND") (class "Default")
      (node (ref "C1") (pin "1") (pinfunction "1_1") (pintype "passive"))
      (node (ref "C10") (pin "2") (pinfunction "2_2") (pintype "passive"))
      (node (ref "C11") (pin "1") (pinfunction "P_1") (pintype "passive"))
      (node (ref "C19") (pin "2") (pinfunction "2_2") (pintype "passive"))
      (node (ref "C2") (pin "1") (pinfunction "1_1") (pintype "passive"))
      (node (ref "C3") (pin "2") (pinfunction "N_2") (pintype "passive"))
      (node (ref "C9") (pin "2") (pinfunction "2_2") (pintype "passive"))
      (node (ref "D3") (pin "4") (pinfunction "K_4") (pintype "passive"))
      (node (ref "R1") (pin "1") (pinfunction "1_1") (pintype "passive"))
      (node (ref "R2") (pin "2") (pinfunction "2_2") (pintype "passive"))
      (node (ref "R9") (pin "2") (pinfunction "2_2") (pintype "passive"))
      (node (ref "TR1") (pin "10") (pinfunction "10_10") (pintype "passive"))
    )
    (net (code "41") (name "SW") (class "Default")
      (node (ref "C16") (pin "1") (pinfunction "1_1") (pintype "passive"))
      (node (ref "Q1") (pin "3") (pinfunction "S_3") (pintype "passive"))
      (node (ref "Q2") (pin "4") (pinfunction "D_4") (pintype "passive"))
      (node (ref "R19") (pin "1") (pinfunction "1_1") (pintype "passive"))
      (node (ref "TR1") (pin "4") (pinfunction "1_4") (pintype "passive"))
      (node (ref "U3") (pin "6") (pinfunction "VS_6") (pintype "passive"))
    )
    (net (code "42") (name "VB") (class "Default")
      (node (ref "C16") (pin "2") (pinfunction "2_2") (pintype "passive"))
      (node (ref "D7") (pin "1") (pinfunction "K_1") (pintype "passive"))
      (node (ref "U3") (pin "8") (pinfunction "VB_8") (pintype "passive"))
    )
    (net (code "43") (name "VCC") (class "Default")
      (node (ref "C17") (pin "2") (pinfunction "2_2") (pintype "passive"))
      (node (ref "C18") (pin "2") (pinfunction "2_2") (pintype "passive"))
      (node (ref "D7") (pin "2") (pinfunction "A_2") (pintype "passive"))
      (node (ref "Q3") (pin "3") (pinfunction "E_3") (pintype "passive"))
      (node (ref "U3") (pin "1") (pinfunction "VCC_1") (pintype "power_in"))
    )
  )
)
